# TDA2003-Amplifier.net
KiCad netlist of a schematic drawn in EAGLE
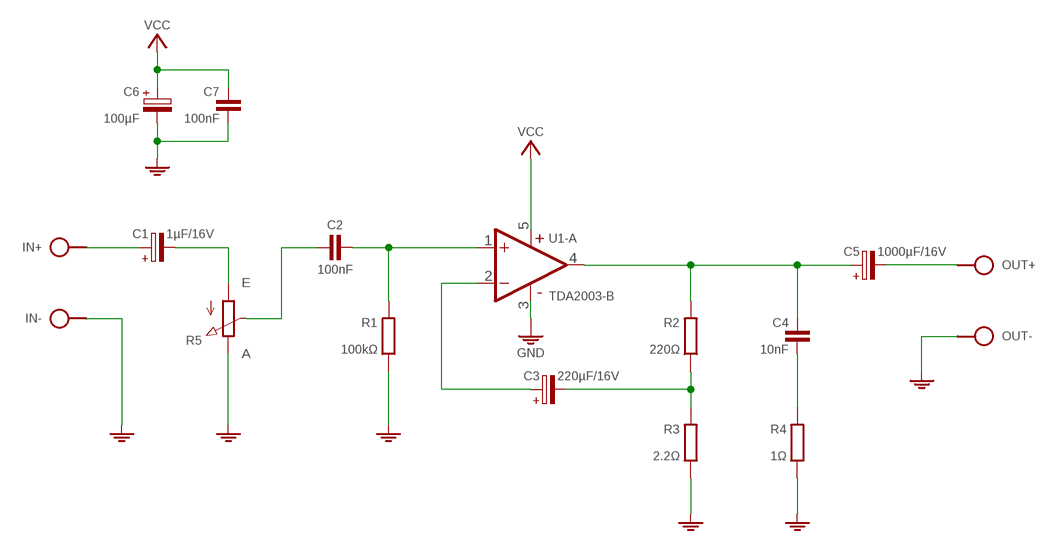
[diagram p0: schematic, sheet 1]

(export (version "E")
  (design (tool "Eeschema 10.0.6"))
  (components
    (comp (ref "C1")
      (value "1µF/16V")
      (footprint "eagle-import:E2,5-5")
      (libsource (lib "eagle-import") (part "CPOL-HE2,5-5"))
    )
    (comp (ref "C2")
      (value "100nF")
      (footprint "eagle-import:C050-024X044")
      (libsource (lib "eagle-import") (part "C-H050-024X044"))
    )
    (comp (ref "C3")
      (value "220µF/16V")
      (footprint "eagle-import:E2,5-5")
      (libsource (lib "eagle-import") (part "CPOL-HE2,5-5"))
    )
    (comp (ref "C4")
      (value "10nF")
      (footprint "eagle-import:C050-020X044_V")
      (libsource (lib "eagle-import") (part "C050-020X044/V"))
    )
    (comp (ref "C5")
      (value "1000µF/16V")
      (footprint "eagle-import:E5-5")
      (libsource (lib "eagle-import") (part "CPOL-HE5-5"))
    )
    (comp (ref "C6")
      (value "100µF")
      (footprint "eagle-import:E5-5_V")
      (libsource (lib "eagle-import") (part "CPOLE5-5/V"))
    )
    (comp (ref "C7")
      (value "100nF")
      (footprint "eagle-import:C050-024X044")
      (libsource (lib "eagle-import") (part "C050-024X044"))
    )
    (comp (ref "IN")
      (value "SPAD+--+")
      (footprint "eagle-import:SPAD-+")
      (libsource (lib "eagle-import") (part "SPAD+--+"))
    )
    (comp (ref "OUT")
      (value "SPAD+-+-")
      (footprint "eagle-import:SPAD+-")
      (libsource (lib "eagle-import") (part "SPAD+-+-"))
    )
    (comp (ref "R1")
      (value "100kΩ")
      (footprint "eagle-import:0204_10")
      (libsource (lib "eagle-import") (part "R0204/10"))
    )
    (comp (ref "R2")
      (value "220Ω")
      (footprint "eagle-import:0204_10")
      (libsource (lib "eagle-import") (part "R0204/10"))
    )
    (comp (ref "R3")
      (value "2.2Ω")
      (footprint "eagle-import:0204_10")
      (libsource (lib "eagle-import") (part "R0204/10"))
    )
    (comp (ref "R4")
      (value "1Ω")
      (footprint "eagle-import:0207_10")
      (libsource (lib "eagle-import") (part "R0207/10"))
    )
    (comp (ref "R5")
      (value "POT")
      (footprint "eagle-import:POT")
      (libsource (lib "eagle-import") (part "POT"))
    )
    (comp (ref "S1")
      (value "VCC_GNDPWR-L")
      (footprint "eagle-import:PWR-L")
      (libsource (lib "eagle-import") (part "VCC_GNDPWR-L"))
    )
    (comp (ref "U1")
      (value "TDA2003-B")
      (footprint "eagle-import:TO220-B5")
      (libsource (lib "eagle-import") (part "TDA2003-B"))
    )
  )
  (nets
    (net (code "1") (name "GND") (class "Default")
      (node (ref "C6") (pin "-") (pinfunction "-_-") (pintype "passive"))
      (node (ref "C7") (pin "2") (pinfunction "2_2") (pintype "passive"))
      (node (ref "IN") (pin "1") (pinfunction "P$1_1") (pintype "passive"))
      (node (ref "OUT") (pin "1") (pinfunction "P$1_1") (pintype "passive"))
      (node (ref "R1") (pin "2") (pinfunction "1_2") (pintype "passive"))
      (node (ref "R3") (pin "2") (pinfunction "1_2") (pintype "passive"))
      (node (ref "R4") (pin "2") (pinfunction "1_2") (pintype "passive"))
      (node (ref "R5") (pin "E") (pinfunction "E_E") (pintype "passive"))
      (node (ref "S1") (pin "1") (pinfunction "GND_1") (pintype "power_in"))
      (node (ref "U1") (pin "3") (pinfunction "V-_3") (pintype "power_in"))
    )
    (net (code "2") (name "Net-(C1-Pad-)") (class "Default")
      (node (ref "C1") (pin "-") (pinfunction "-_-") (pintype "passive"))
      (node (ref "R5") (pin "A") (pinfunction "A_A") (pintype "passive"))
    )
    (net (code "3") (name "Net-(C2-Pad1)") (class "Default")
      (node (ref "C2") (pin "1") (pinfunction "1_1") (pintype "passive"))
      (node (ref "R5") (pin "S") (pinfunction "S_S") (pintype "passive"))
    )
    (net (code "4") (name "Net-(INA-P$1)") (class "Default")
      (node (ref "C1") (pin "+") (pinfunction "+_+") (pintype "passive"))
      (node (ref "IN") (pin "2") (pinfunction "P$1_2") (pintype "passive"))
    )
    (net (code "5") (name "Net-(OUTA-P$1)") (class "Default")
      (node (ref "C5") (pin "-") (pinfunction "-_-") (pintype "passive"))
      (node (ref "OUT") (pin "2") (pinfunction "P$1_2") (pintype "passive"))
    )
    (net (code "6") (name "Net-(R1-2)") (class "Default")
      (node (ref "C2") (pin "2") (pinfunction "2_2") (pintype "passive"))
      (node (ref "R1") (pin "1") (pinfunction "2_1") (pintype "passive"))
      (node (ref "U1") (pin "1") (pinfunction "+IN_1") (pintype "input"))
    )
    (net (code "7") (name "Net-(R2-1)") (class "Default")
      (node (ref "C3") (pin "-") (pinfunction "-_-") (pintype "passive"))
      (node (ref "R2") (pin "2") (pinfunction "1_2") (pintype "passive"))
      (node (ref "R3") (pin "1") (pinfunction "2_1") (pintype "passive"))
    )
    (net (code "8") (name "Net-(R2-2)") (class "Default")
      (node (ref "C4") (pin "1") (pinfunction "1_1") (pintype "passive"))
      (node (ref "C5") (pin "+") (pinfunction "+_+") (pintype "passive"))
      (node (ref "R2") (pin "1") (pinfunction "2_1") (pintype "passive"))
      (node (ref "U1") (pin "4") (pinfunction "OUT_4") (pintype "output"))
    )
    (net (code "9") (name "Net-(R4-2)") (class "Default")
      (node (ref "C4") (pin "2") (pinfunction "2_2") (pintype "passive"))
      (node (ref "R4") (pin "1") (pinfunction "2_1") (pintype "passive"))
    )
    (net (code "10") (name "Net-(U1A--IN)") (class "Default")
      (node (ref "C3") (pin "+") (pinfunction "+_+") (pintype "passive"))
      (node (ref "U1") (pin "2") (pinfunction "-IN_2") (pintype "input"))
    )
    (net (code "11") (name "VCC") (class "Default")
      (node (ref "C6") (pin "+") (pinfunction "+_+") (pintype "passive"))
      (node (ref "C7") (pin "1") (pinfunction "1_1") (pintype "passive"))
      (node (ref "S1") (pin "2") (pinfunction "VCC_2") (pintype "power_in"))
      (node (ref "U1") (pin "5") (pinfunction "V+_5") (pintype "power_in"))
    )
  )
)
